# Obstacle_Sensors.net
KiCad netlist of a schematic drawn in Altium Designer
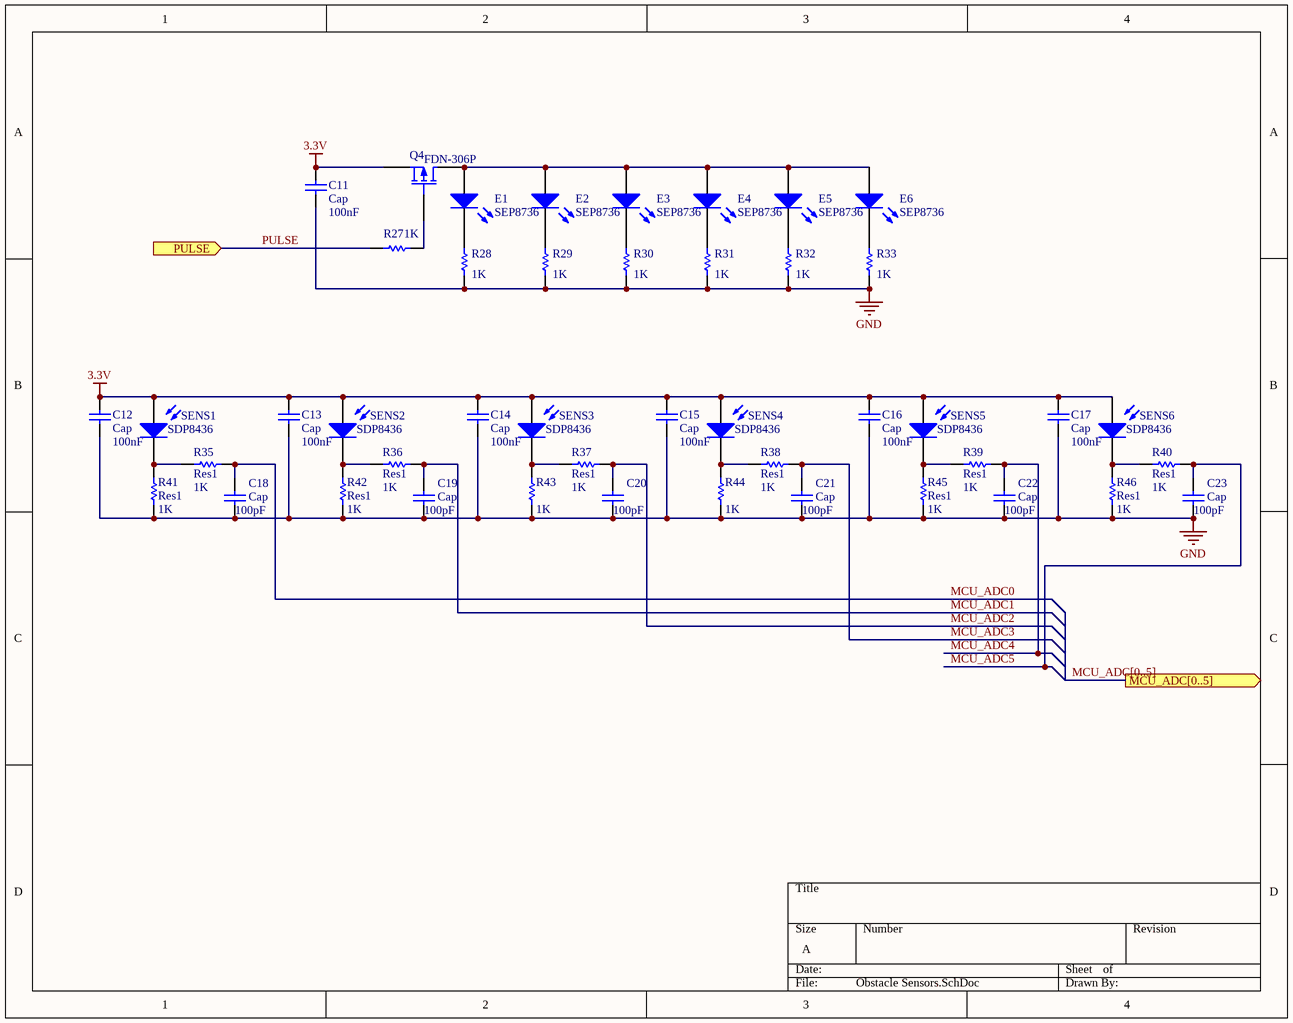
[diagram p0: Obstacle Sensors.SchDoc]

(export (version "E")
  (design (tool "Eeschema 10.0.6"))
  (components
    (comp (ref "C11")
      (value "Cap")
      (footprint "0603_CAP")
      (description "Capacitor")
      (fields (field (name "ALTIUM_VALUE") "100nF") (field (name "PUBLISHER") "Altium Limited"))
      (libsource (lib "Miscellaneous Devices") (part "Cap"))
    )
    (comp (ref "C12")
      (value "Cap")
      (footprint "0603_CAP")
      (description "Capacitor")
      (fields (field (name "ALTIUM_VALUE") "100nF") (field (name "PUBLISHER") "Altium Limited"))
      (libsource (lib "Miscellaneous Devices") (part "Cap"))
    )
    (comp (ref "C13")
      (value "Cap")
      (footprint "0603_CAP")
      (description "Capacitor")
      (fields (field (name "ALTIUM_VALUE") "100nF") (field (name "PUBLISHER") "Altium Limited"))
      (libsource (lib "Miscellaneous Devices") (part "Cap"))
    )
    (comp (ref "C14")
      (value "Cap")
      (footprint "0603_CAP")
      (description "Capacitor")
      (fields (field (name "ALTIUM_VALUE") "100nF") (field (name "PUBLISHER") "Altium Limited"))
      (libsource (lib "Miscellaneous Devices") (part "Cap"))
    )
    (comp (ref "C15")
      (value "Cap")
      (footprint "0603_CAP")
      (description "Capacitor")
      (fields (field (name "ALTIUM_VALUE") "100nF") (field (name "PUBLISHER") "Altium Limited"))
      (libsource (lib "Miscellaneous Devices") (part "Cap"))
    )
    (comp (ref "C16")
      (value "Cap")
      (footprint "0603_CAP")
      (description "Capacitor")
      (fields (field (name "ALTIUM_VALUE") "100nF") (field (name "PUBLISHER") "Altium Limited"))
      (libsource (lib "Miscellaneous Devices") (part "Cap"))
    )
    (comp (ref "C17")
      (value "Cap")
      (footprint "0603_CAP")
      (description "Capacitor")
      (fields (field (name "ALTIUM_VALUE") "100nF") (field (name "PUBLISHER") "Altium Limited"))
      (libsource (lib "Miscellaneous Devices") (part "Cap"))
    )
    (comp (ref "C18")
      (value "Cap")
      (footprint "0603_CAP")
      (description "Capacitor")
      (fields (field (name "ALTIUM_VALUE") "100pF") (field (name "PUBLISHER") "Altium Limited"))
      (libsource (lib "Miscellaneous Devices") (part "Cap"))
    )
    (comp (ref "C19")
      (value "Cap")
      (footprint "0603_CAP")
      (description "Capacitor")
      (fields (field (name "ALTIUM_VALUE") "100pF") (field (name "PUBLISHER") "Altium Limited"))
      (libsource (lib "Miscellaneous Devices") (part "Cap"))
    )
    (comp (ref "C20")
      (value "100pF")
      (footprint "0603_CAP")
      (description "Capacitor")
      (fields (field (name "Comment") "Cap") (field (name "PUBLISHER") "Altium Limited"))
      (libsource (lib "Miscellaneous Devices") (part "Cap"))
    )
    (comp (ref "C21")
      (value "Cap")
      (footprint "0603_CAP")
      (description "Capacitor")
      (fields (field (name "ALTIUM_VALUE") "100pF") (field (name "PUBLISHER") "Altium Limited"))
      (libsource (lib "Miscellaneous Devices") (part "Cap"))
    )
    (comp (ref "C22")
      (value "Cap")
      (footprint "0603_CAP")
      (description "Capacitor")
      (fields (field (name "ALTIUM_VALUE") "100pF") (field (name "PUBLISHER") "Altium Limited"))
      (libsource (lib "Miscellaneous Devices") (part "Cap"))
    )
    (comp (ref "C23")
      (value "Cap")
      (footprint "0603_CAP")
      (description "Capacitor")
      (fields (field (name "ALTIUM_VALUE") "100pF") (field (name "PUBLISHER") "Altium Limited"))
      (libsource (lib "Miscellaneous Devices") (part "Cap"))
    )
    (comp (ref "E1")
      (value "SEP8736")
      (footprint "T-1SL")
      (description "Typical INFRARED GaAs LED")
      (fields (field (name "PUBLISHER") "Altium Limited"))
      (libsource (lib "Miscellaneous Devices") (part "LED0"))
    )
    (comp (ref "E2")
      (value "SEP8736")
      (footprint "T-1SL")
      (description "Typical INFRARED GaAs LED")
      (fields (field (name "PUBLISHER") "Altium Limited"))
      (libsource (lib "Miscellaneous Devices") (part "LED0"))
    )
    (comp (ref "E3")
      (value "SEP8736")
      (footprint "T-1SL")
      (description "Typical INFRARED GaAs LED")
      (fields (field (name "PUBLISHER") "Altium Limited"))
      (libsource (lib "Miscellaneous Devices") (part "LED0"))
    )
    (comp (ref "E4")
      (value "SEP8736")
      (footprint "T-1SL")
      (description "Typical INFRARED GaAs LED")
      (fields (field (name "PUBLISHER") "Altium Limited"))
      (libsource (lib "Miscellaneous Devices") (part "LED0"))
    )
    (comp (ref "E5")
      (value "SEP8736")
      (footprint "T-1SL")
      (description "Typical INFRARED GaAs LED")
      (fields (field (name "PUBLISHER") "Altium Limited"))
      (libsource (lib "Miscellaneous Devices") (part "LED0"))
    )
    (comp (ref "E6")
      (value "SEP8736")
      (footprint "T-1SL")
      (description "Typical INFRARED GaAs LED")
      (fields (field (name "PUBLISHER") "Altium Limited"))
      (libsource (lib "Miscellaneous Devices") (part "LED0"))
    )
    (comp (ref "Q4")
      (value "FDN-306P")
      (footprint "SOT-23")
      (description "P-Channel MOSFET")
      (fields
        (field (name "MANUFACTURER") "Fairchild Semiconductor")
        (field (name "MANUFACTURER PART NUMBER") "FDN306P")
        (field (name "PUBLISHER") "Altium Limited")
      )
      (libsource (lib "Miscellaneous Devices") (part "MOSFET-P"))
    )
    (comp (ref "R27")
      (value "1K")
      (footprint "0603_RES")
      (description "Resistor")
      (fields (field (name "Comment") "Res1") (field (name "PUBLISHER") "Altium Limited"))
      (libsource (lib "Miscellaneous Devices") (part "Res1"))
    )
    (comp (ref "R28")
      (value "1K")
      (footprint "0603_RES")
      (description "Resistor")
      (fields (field (name "Comment") "Res1") (field (name "PUBLISHER") "Altium Limited"))
      (libsource (lib "Miscellaneous Devices") (part "Res1"))
    )
    (comp (ref "R29")
      (value "1K")
      (footprint "0603_RES")
      (description "Resistor")
      (fields (field (name "Comment") "Res1") (field (name "PUBLISHER") "Altium Limited"))
      (libsource (lib "Miscellaneous Devices") (part "Res1"))
    )
    (comp (ref "R30")
      (value "1K")
      (footprint "0603_RES")
      (description "Resistor")
      (fields (field (name "Comment") "Res1") (field (name "PUBLISHER") "Altium Limited"))
      (libsource (lib "Miscellaneous Devices") (part "Res1"))
    )
    (comp (ref "R31")
      (value "1K")
      (footprint "0603_RES")
      (description "Resistor")
      (fields (field (name "Comment") "Res1") (field (name "PUBLISHER") "Altium Limited"))
      (libsource (lib "Miscellaneous Devices") (part "Res1"))
    )
    (comp (ref "R32")
      (value "1K")
      (footprint "0603_RES")
      (description "Resistor")
      (fields (field (name "Comment") "Res1") (field (name "PUBLISHER") "Altium Limited"))
      (libsource (lib "Miscellaneous Devices") (part "Res1"))
    )
    (comp (ref "R33")
      (value "1K")
      (footprint "0603_RES")
      (description "Resistor")
      (fields (field (name "Comment") "Res1") (field (name "PUBLISHER") "Altium Limited"))
      (libsource (lib "Miscellaneous Devices") (part "Res1"))
    )
    (comp (ref "R35")
      (value "Res1")
      (footprint "0603_RES")
      (description "Resistor")
      (fields (field (name "ALTIUM_VALUE") "1K") (field (name "PUBLISHER") "Altium Limited"))
      (libsource (lib "Miscellaneous Devices") (part "Res1"))
    )
    (comp (ref "R36")
      (value "Res1")
      (footprint "0603_RES")
      (description "Resistor")
      (fields (field (name "ALTIUM_VALUE") "1K") (field (name "PUBLISHER") "Altium Limited"))
      (libsource (lib "Miscellaneous Devices") (part "Res1"))
    )
    (comp (ref "R37")
      (value "Res1")
      (footprint "0603_RES")
      (description "Resistor")
      (fields (field (name "ALTIUM_VALUE") "1K") (field (name "PUBLISHER") "Altium Limited"))
      (libsource (lib "Miscellaneous Devices") (part "Res1"))
    )
    (comp (ref "R38")
      (value "Res1")
      (footprint "0603_RES")
      (description "Resistor")
      (fields (field (name "ALTIUM_VALUE") "1K") (field (name "PUBLISHER") "Altium Limited"))
      (libsource (lib "Miscellaneous Devices") (part "Res1"))
    )
    (comp (ref "R39")
      (value "Res1")
      (footprint "0603_RES")
      (description "Resistor")
      (fields (field (name "ALTIUM_VALUE") "1K") (field (name "PUBLISHER") "Altium Limited"))
      (libsource (lib "Miscellaneous Devices") (part "Res1"))
    )
    (comp (ref "R40")
      (value "Res1")
      (footprint "0603_RES")
      (description "Resistor")
      (fields (field (name "ALTIUM_VALUE") "1K") (field (name "PUBLISHER") "Altium Limited"))
      (libsource (lib "Miscellaneous Devices") (part "Res1"))
    )
    (comp (ref "R41")
      (value "Res1")
      (footprint "0603_RES")
      (description "Resistor")
      (fields (field (name "ALTIUM_VALUE") "1K") (field (name "PUBLISHER") "Altium Limited"))
      (libsource (lib "Miscellaneous Devices") (part "Res1"))
    )
    (comp (ref "R42")
      (value "Res1")
      (footprint "0603_RES")
      (description "Resistor")
      (fields (field (name "ALTIUM_VALUE") "1K") (field (name "PUBLISHER") "Altium Limited"))
      (libsource (lib "Miscellaneous Devices") (part "Res1"))
    )
    (comp (ref "R43")
      (value "1K")
      (footprint "0603_RES")
      (description "Resistor")
      (fields (field (name "Comment") "Res1") (field (name "PUBLISHER") "Altium Limited"))
      (libsource (lib "Miscellaneous Devices") (part "Res1"))
    )
    (comp (ref "R44")
      (value "1K")
      (footprint "0603_RES")
      (description "Resistor")
      (fields (field (name "Comment") "Res1") (field (name "PUBLISHER") "Altium Limited"))
      (libsource (lib "Miscellaneous Devices") (part "Res1"))
    )
    (comp (ref "R45")
      (value "Res1")
      (footprint "0603_RES")
      (description "Resistor")
      (fields (field (name "ALTIUM_VALUE") "1K") (field (name "PUBLISHER") "Altium Limited"))
      (libsource (lib "Miscellaneous Devices") (part "Res1"))
    )
    (comp (ref "R46")
      (value "Res1")
      (footprint "0603_RES")
      (description "Resistor")
      (fields (field (name "ALTIUM_VALUE") "1K") (field (name "PUBLISHER") "Altium Limited"))
      (libsource (lib "Miscellaneous Devices") (part "Res1"))
    )
    (comp (ref "SENS1")
      (value "SDP8436")
      (footprint "T-1SL")
      (description "Photosensitive Diode")
      (fields (field (name "PUBLISHER") "Altium Limited"))
      (libsource (lib "Miscellaneous Devices") (part "Photo Sen"))
    )
    (comp (ref "SENS2")
      (value "SDP8436")
      (footprint "T-1SL")
      (description "Photosensitive Diode")
      (fields (field (name "PUBLISHER") "Altium Limited"))
      (libsource (lib "Miscellaneous Devices") (part "Photo Sen"))
    )
    (comp (ref "SENS3")
      (value "SDP8436")
      (footprint "T-1SL")
      (description "Photosensitive Diode")
      (fields (field (name "PUBLISHER") "Altium Limited"))
      (libsource (lib "Miscellaneous Devices") (part "Photo Sen"))
    )
    (comp (ref "SENS4")
      (value "SDP8436")
      (footprint "T-1SL")
      (description "Photosensitive Diode")
      (fields (field (name "PUBLISHER") "Altium Limited"))
      (libsource (lib "Miscellaneous Devices") (part "Photo Sen"))
    )
    (comp (ref "SENS5")
      (value "SDP8436")
      (footprint "T-1SL")
      (description "Photosensitive Diode")
      (fields (field (name "PUBLISHER") "Altium Limited"))
      (libsource (lib "Miscellaneous Devices") (part "Photo Sen"))
    )
    (comp (ref "SENS6")
      (value "SDP8436")
      (footprint "T-1SL")
      (description "Photosensitive Diode")
      (fields (field (name "PUBLISHER") "Altium Limited"))
      (libsource (lib "Miscellaneous Devices") (part "Photo Sen"))
    )
  )
  (nets
    (net (code "1") (name "/MCU_ADC0") (class "Default")
      (node (ref "C18") (pin "2") (pinfunction "2_2") (pintype "passive"))
      (node (ref "R35") (pin "1") (pinfunction "1_1") (pintype "passive"))
    )
    (net (code "2") (name "/MCU_ADC1") (class "Default")
      (node (ref "C19") (pin "2") (pinfunction "2_2") (pintype "passive"))
      (node (ref "R36") (pin "1") (pinfunction "1_1") (pintype "passive"))
    )
    (net (code "3") (name "/MCU_ADC2") (class "Default")
      (node (ref "C20") (pin "2") (pinfunction "2_2") (pintype "passive"))
      (node (ref "R37") (pin "1") (pinfunction "1_1") (pintype "passive"))
    )
    (net (code "4") (name "/MCU_ADC3") (class "Default")
      (node (ref "C21") (pin "2") (pinfunction "2_2") (pintype "passive"))
      (node (ref "R38") (pin "1") (pinfunction "1_1") (pintype "passive"))
    )
    (net (code "5") (name "/MCU_ADC4") (class "Default")
      (node (ref "C22") (pin "2") (pinfunction "2_2") (pintype "passive"))
      (node (ref "R39") (pin "1") (pinfunction "1_1") (pintype "passive"))
    )
    (net (code "6") (name "/MCU_ADC5") (class "Default")
      (node (ref "C23") (pin "2") (pinfunction "2_2") (pintype "passive"))
      (node (ref "R40") (pin "1") (pinfunction "1_1") (pintype "passive"))
    )
    (net (code "8") (name "/PULSE") (class "Default")
      (node (ref "R27") (pin "1") (pinfunction "1_1") (pintype "passive"))
    )
    (net (code "9") (name "3.3V") (class "Default")
      (node (ref "C11") (pin "2") (pinfunction "2_2") (pintype "passive"))
      (node (ref "C12") (pin "2") (pinfunction "2_2") (pintype "passive"))
      (node (ref "C13") (pin "2") (pinfunction "2_2") (pintype "passive"))
      (node (ref "C14") (pin "2") (pinfunction "2_2") (pintype "passive"))
      (node (ref "C15") (pin "2") (pinfunction "2_2") (pintype "passive"))
      (node (ref "C16") (pin "2") (pinfunction "2_2") (pintype "passive"))
      (node (ref "C17") (pin "2") (pinfunction "2_2") (pintype "passive"))
      (node (ref "Q4") (pin "3") (pinfunction "S_3") (pintype "passive"))
      (node (ref "SENS1") (pin "1") (pinfunction "A_1") (pintype "passive"))
      (node (ref "SENS2") (pin "1") (pinfunction "A_1") (pintype "passive"))
      (node (ref "SENS3") (pin "1") (pinfunction "A_1") (pintype "passive"))
      (node (ref "SENS4") (pin "1") (pinfunction "A_1") (pintype "passive"))
      (node (ref "SENS5") (pin "1") (pinfunction "A_1") (pintype "passive"))
      (node (ref "SENS6") (pin "1") (pinfunction "A_1") (pintype "passive"))
    )
    (net (code "10") (name "GND") (class "Default")
      (node (ref "C11") (pin "1") (pinfunction "1_1") (pintype "passive"))
      (node (ref "C12") (pin "1") (pinfunction "1_1") (pintype "passive"))
      (node (ref "C13") (pin "1") (pinfunction "1_1") (pintype "passive"))
      (node (ref "C14") (pin "1") (pinfunction "1_1") (pintype "passive"))
      (node (ref "C15") (pin "1") (pinfunction "1_1") (pintype "passive"))
      (node (ref "C16") (pin "1") (pinfunction "1_1") (pintype "passive"))
      (node (ref "C17") (pin "1") (pinfunction "1_1") (pintype "passive"))
      (node (ref "C18") (pin "1") (pinfunction "1_1") (pintype "passive"))
      (node (ref "C19") (pin "1") (pinfunction "1_1") (pintype "passive"))
      (node (ref "C20") (pin "1") (pinfunction "1_1") (pintype "passive"))
      (node (ref "C21") (pin "1") (pinfunction "1_1") (pintype "passive"))
      (node (ref "C22") (pin "1") (pinfunction "1_1") (pintype "passive"))
      (node (ref "C23") (pin "1") (pinfunction "1_1") (pintype "passive"))
      (node (ref "R28") (pin "1") (pinfunction "1_1") (pintype "passive"))
      (node (ref "R29") (pin "1") (pinfunction "1_1") (pintype "passive"))
      (node (ref "R30") (pin "1") (pinfunction "1_1") (pintype "passive"))
      (node (ref "R31") (pin "1") (pinfunction "1_1") (pintype "passive"))
      (node (ref "R32") (pin "1") (pinfunction "1_1") (pintype "passive"))
      (node (ref "R33") (pin "1") (pinfunction "1_1") (pintype "passive"))
      (node (ref "R41") (pin "1") (pinfunction "1_1") (pintype "passive"))
      (node (ref "R42") (pin "1") (pinfunction "1_1") (pintype "passive"))
      (node (ref "R43") (pin "1") (pinfunction "1_1") (pintype "passive"))
      (node (ref "R44") (pin "1") (pinfunction "1_1") (pintype "passive"))
      (node (ref "R45") (pin "1") (pinfunction "1_1") (pintype "passive"))
      (node (ref "R46") (pin "1") (pinfunction "1_1") (pintype "passive"))
    )
    (net (code "11") (name "Net-(E1-A)") (class "Default")
      (node (ref "E1") (pin "1") (pinfunction "A_1") (pintype "passive"))
      (node (ref "E2") (pin "1") (pinfunction "A_1") (pintype "passive"))
      (node (ref "E3") (pin "1") (pinfunction "A_1") (pintype "passive"))
      (node (ref "E4") (pin "1") (pinfunction "A_1") (pintype "passive"))
      (node (ref "E5") (pin "1") (pinfunction "A_1") (pintype "passive"))
      (node (ref "E6") (pin "1") (pinfunction "A_1") (pintype "passive"))
      (node (ref "Q4") (pin "1") (pinfunction "D_1") (pintype "passive"))
    )
    (net (code "12") (name "Net-(E1-K)") (class "Default")
      (node (ref "E1") (pin "2") (pinfunction "K_2") (pintype "passive"))
      (node (ref "R28") (pin "2") (pinfunction "2_2") (pintype "passive"))
    )
    (net (code "13") (name "Net-(E2-K)") (class "Default")
      (node (ref "E2") (pin "2") (pinfunction "K_2") (pintype "passive"))
      (node (ref "R29") (pin "2") (pinfunction "2_2") (pintype "passive"))
    )
    (net (code "14") (name "Net-(E3-K)") (class "Default")
      (node (ref "E3") (pin "2") (pinfunction "K_2") (pintype "passive"))
      (node (ref "R30") (pin "2") (pinfunction "2_2") (pintype "passive"))
    )
    (net (code "15") (name "Net-(E4-K)") (class "Default")
      (node (ref "E4") (pin "2") (pinfunction "K_2") (pintype "passive"))
      (node (ref "R31") (pin "2") (pinfunction "2_2") (pintype "passive"))
    )
    (net (code "16") (name "Net-(E5-K)") (class "Default")
      (node (ref "E5") (pin "2") (pinfunction "K_2") (pintype "passive"))
      (node (ref "R32") (pin "2") (pinfunction "2_2") (pintype "passive"))
    )
    (net (code "17") (name "Net-(E6-K)") (class "Default")
      (node (ref "E6") (pin "2") (pinfunction "K_2") (pintype "passive"))
      (node (ref "R33") (pin "2") (pinfunction "2_2") (pintype "passive"))
    )
    (net (code "18") (name "Net-(Q4-G)") (class "Default")
      (node (ref "Q4") (pin "2") (pinfunction "G_2") (pintype "passive"))
      (node (ref "R27") (pin "2") (pinfunction "2_2") (pintype "passive"))
    )
    (net (code "19") (name "Net-(SENS1-K)") (class "Default")
      (node (ref "R35") (pin "2") (pinfunction "2_2") (pintype "passive"))
      (node (ref "R41") (pin "2") (pinfunction "2_2") (pintype "passive"))
      (node (ref "SENS1") (pin "2") (pinfunction "K_2") (pintype "passive"))
    )
    (net (code "20") (name "Net-(SENS2-K)") (class "Default")
      (node (ref "R36") (pin "2") (pinfunction "2_2") (pintype "passive"))
      (node (ref "R42") (pin "2") (pinfunction "2_2") (pintype "passive"))
      (node (ref "SENS2") (pin "2") (pinfunction "K_2") (pintype "passive"))
    )
    (net (code "21") (name "Net-(SENS3-K)") (class "Default")
      (node (ref "R37") (pin "2") (pinfunction "2_2") (pintype "passive"))
      (node (ref "R43") (pin "2") (pinfunction "2_2") (pintype "passive"))
      (node (ref "SENS3") (pin "2") (pinfunction "K_2") (pintype "passive"))
    )
    (net (code "22") (name "Net-(SENS4-K)") (class "Default")
      (node (ref "R38") (pin "2") (pinfunction "2_2") (pintype "passive"))
      (node (ref "R44") (pin "2") (pinfunction "2_2") (pintype "passive"))
      (node (ref "SENS4") (pin "2") (pinfunction "K_2") (pintype "passive"))
    )
    (net (code "23") (name "Net-(SENS5-K)") (class "Default")
      (node (ref "R39") (pin "2") (pinfunction "2_2") (pintype "passive"))
      (node (ref "R45") (pin "2") (pinfunction "2_2") (pintype "passive"))
      (node (ref "SENS5") (pin "2") (pinfunction "K_2") (pintype "passive"))
    )
    (net (code "24") (name "Net-(SENS6-K)") (class "Default")
      (node (ref "R40") (pin "2") (pinfunction "2_2") (pintype "passive"))
      (node (ref "R46") (pin "2") (pinfunction "2_2") (pintype "passive"))
      (node (ref "SENS6") (pin "2") (pinfunction "K_2") (pintype "passive"))
    )
  )
)
